# Main_PCB_v2.net
KiCad netlist of a schematic drawn in EAGLE
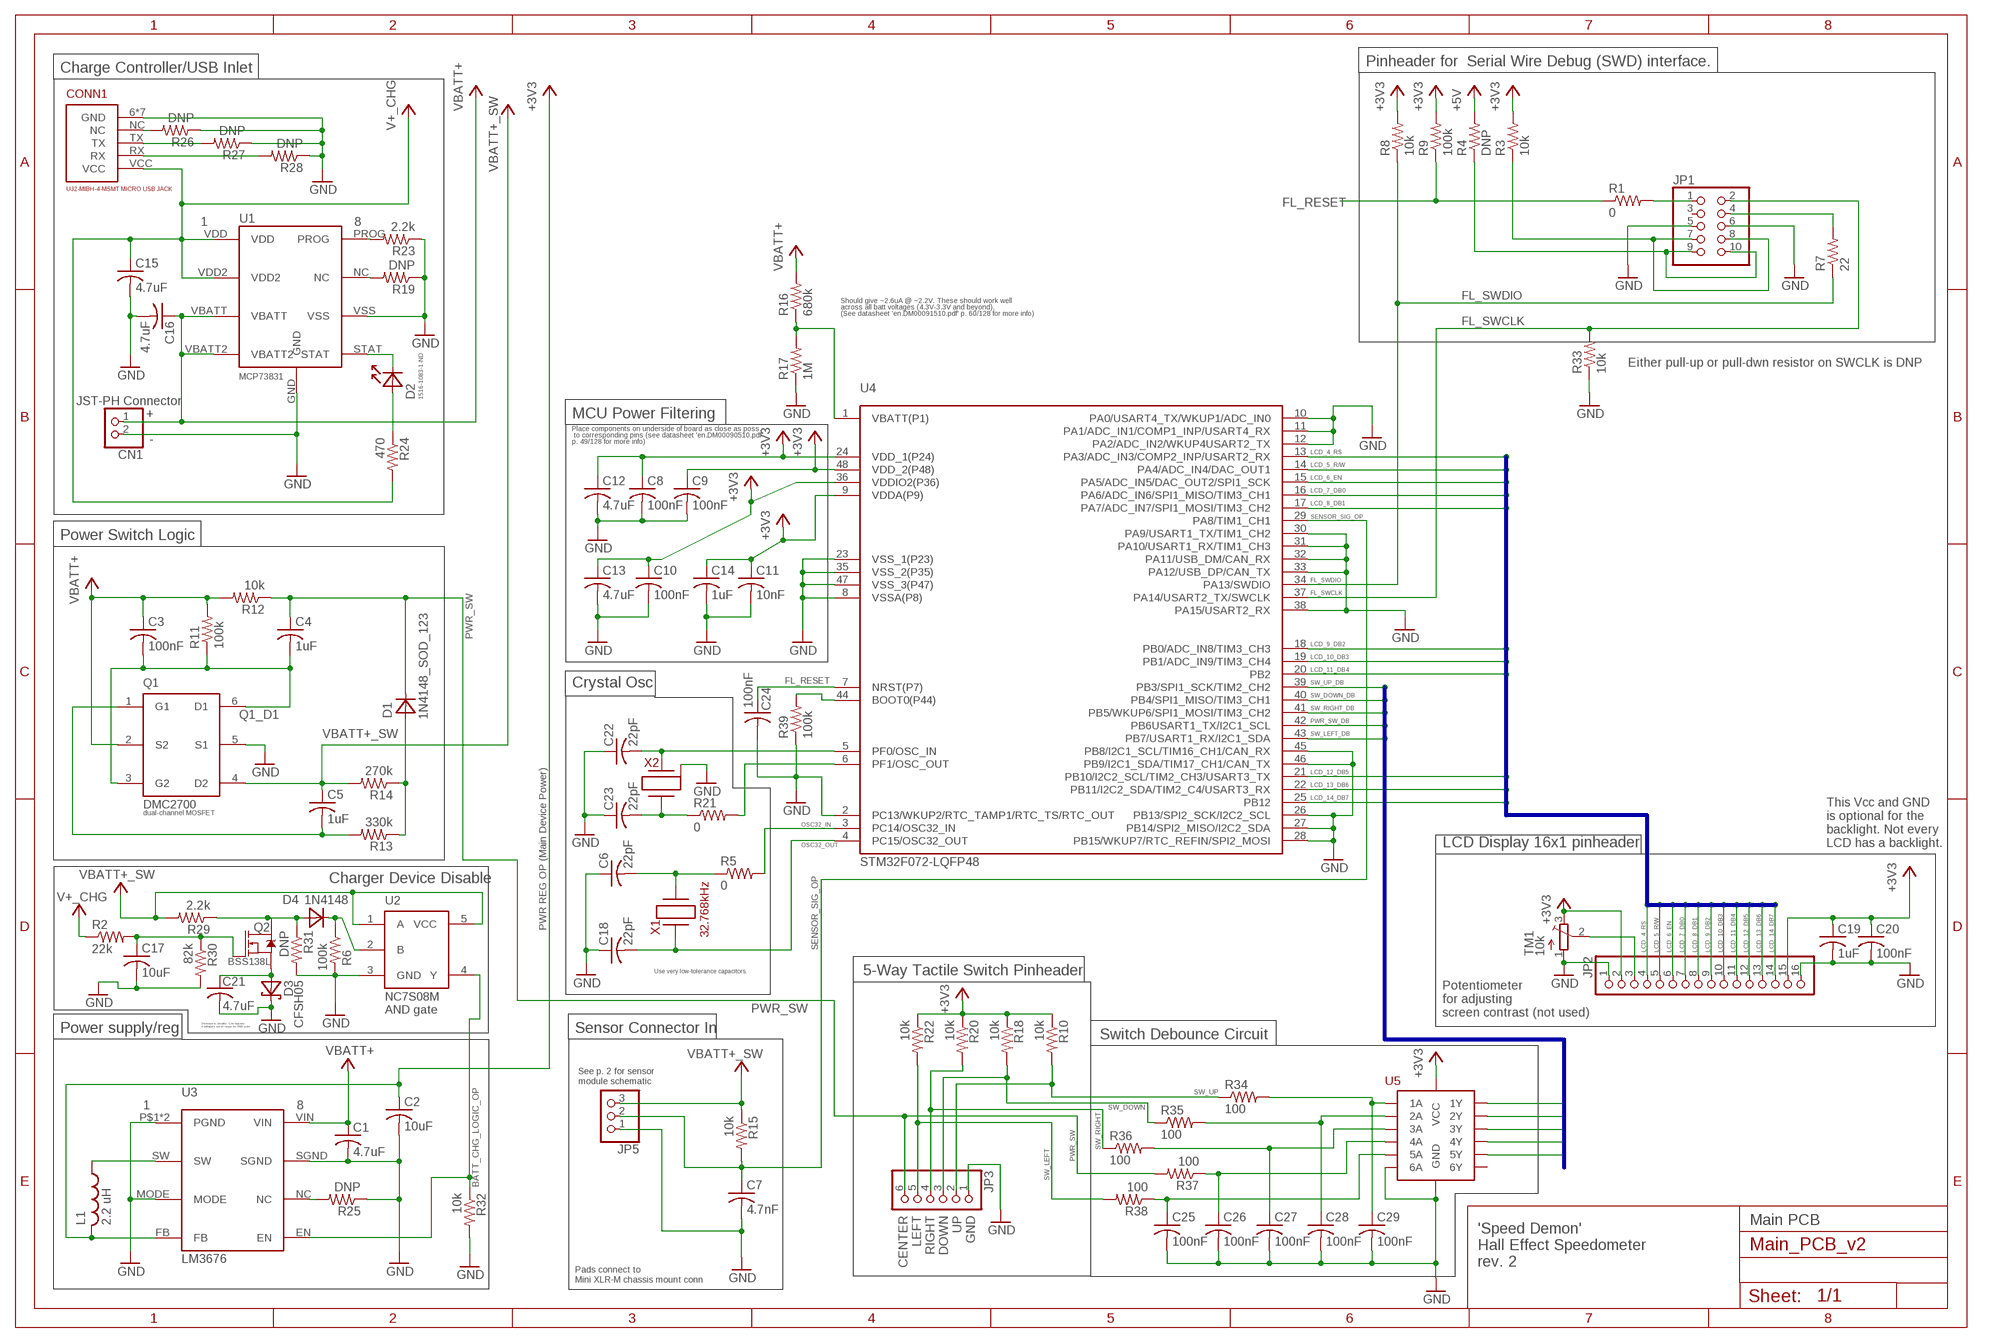
[diagram p0: schematic, sheet 1]

(export (version "E")
  (design (tool "Eeschema 10.0.6"))
  (components
    (comp (ref "C1")
      (value "4.7uF")
      (footprint "eagle-import:C_0805")
      (libsource (lib "eagle-import") (part "C_0805_NP"))
    )
    (comp (ref "C2")
      (value "10uF")
      (footprint "eagle-import:C_0805")
      (libsource (lib "eagle-import") (part "C_0805_NP"))
    )
    (comp (ref "C3")
      (value "100nF")
      (footprint "eagle-import:C_0805")
      (libsource (lib "eagle-import") (part "C_0805_NP"))
    )
    (comp (ref "C4")
      (value "1uF")
      (footprint "eagle-import:C_0805")
      (libsource (lib "eagle-import") (part "C_0805_NP"))
    )
    (comp (ref "C5")
      (value "1uF")
      (footprint "eagle-import:C_0805")
      (libsource (lib "eagle-import") (part "C_0805_NP"))
    )
    (comp (ref "C6")
      (value "22pF")
      (footprint "eagle-import:C_0805")
      (libsource (lib "eagle-import") (part "LCRD_SMD_generics_C_0805_NP"))
    )
    (comp (ref "C7")
      (value "4.7nF")
      (footprint "eagle-import:C_0805")
      (libsource (lib "eagle-import") (part "C_0805_NP"))
    )
    (comp (ref "C8")
      (value "100nF")
      (footprint "eagle-import:C_0805")
      (libsource (lib "eagle-import") (part "C_0805_NP"))
    )
    (comp (ref "C9")
      (value "100nF")
      (footprint "eagle-import:C_0805")
      (libsource (lib "eagle-import") (part "C_0805_NP"))
    )
    (comp (ref "C10")
      (value "100nF")
      (footprint "eagle-import:C_0805")
      (libsource (lib "eagle-import") (part "C_0805_NP"))
    )
    (comp (ref "C11")
      (value "10nF")
      (footprint "eagle-import:C_0805")
      (libsource (lib "eagle-import") (part "C_0805_NP"))
    )
    (comp (ref "C12")
      (value "4.7uF")
      (footprint "eagle-import:C_0805")
      (libsource (lib "eagle-import") (part "C_0805_NP"))
    )
    (comp (ref "C13")
      (value "4.7uF")
      (footprint "eagle-import:C_0805")
      (libsource (lib "eagle-import") (part "C_0805_NP"))
    )
    (comp (ref "C14")
      (value "1uF")
      (footprint "eagle-import:C_0805")
      (libsource (lib "eagle-import") (part "C_0805_NP"))
    )
    (comp (ref "C15")
      (value "4.7uF")
      (footprint "eagle-import:C_0805")
      (libsource (lib "eagle-import") (part "C_0805_NP"))
    )
    (comp (ref "C16")
      (value "4.7uF")
      (footprint "eagle-import:C_0805")
      (libsource (lib "eagle-import") (part "C_0805_NP"))
    )
    (comp (ref "C17")
      (value "10uF")
      (footprint "eagle-import:C_0805")
      (libsource (lib "eagle-import") (part "C_0805_NP"))
    )
    (comp (ref "C18")
      (value "22pF")
      (footprint "eagle-import:C_0805")
      (libsource (lib "eagle-import") (part "LCRD_SMD_generics_C_0805_NP"))
    )
    (comp (ref "C19")
      (value "1uF")
      (footprint "eagle-import:C_0805")
      (libsource (lib "eagle-import") (part "C_0805_NP"))
    )
    (comp (ref "C20")
      (value "100nF")
      (footprint "eagle-import:C_0805")
      (libsource (lib "eagle-import") (part "C_0805_NP"))
    )
    (comp (ref "C21")
      (value "4.7uF")
      (footprint "eagle-import:C_0805")
      (libsource (lib "eagle-import") (part "C_0805_NP"))
    )
    (comp (ref "C22")
      (value "22pF")
      (footprint "eagle-import:C_0805")
      (libsource (lib "eagle-import") (part "LCRD_SMD_generics_C_0805_NP"))
    )
    (comp (ref "C23")
      (value "22pF")
      (footprint "eagle-import:C_0805")
      (libsource (lib "eagle-import") (part "LCRD_SMD_generics_C_0805_NP"))
    )
    (comp (ref "C24")
      (value "100nF")
      (footprint "eagle-import:C_0805")
      (libsource (lib "eagle-import") (part "C_0805_NP"))
    )
    (comp (ref "C25")
      (value "100nF")
      (footprint "eagle-import:C_0805")
      (libsource (lib "eagle-import") (part "C_0805_NP"))
    )
    (comp (ref "C26")
      (value "100nF")
      (footprint "eagle-import:C_0805")
      (libsource (lib "eagle-import") (part "C_0805_NP"))
    )
    (comp (ref "C27")
      (value "100nF")
      (footprint "eagle-import:C_0805")
      (libsource (lib "eagle-import") (part "C_0805_NP"))
    )
    (comp (ref "C28")
      (value "100nF")
      (footprint "eagle-import:C_0805")
      (libsource (lib "eagle-import") (part "C_0805_NP"))
    )
    (comp (ref "C29")
      (value "100nF")
      (footprint "eagle-import:C_0805")
      (libsource (lib "eagle-import") (part "C_0805_NP"))
    )
    (comp (ref "CN1")
      (value "JST_2PIN-SMT-RA")
      (footprint "eagle-import:JST-PH-2-SMT-RA")
      (libsource (lib "eagle-import") (part "JST_2PIN-SMT-RA"))
    )
    (comp (ref "CONN1")
      (value "USB_JACK_102-4008-1-ND_USB-MICRO-B")
      (footprint "eagle-import:USB_JACK_102-4008-1-ND_UJ2-MIBH-4-MSMT-TR")
      (libsource (lib "eagle-import") (part "USB_JACK_102-4008-1-ND_USB-MICRO-B"))
    )
    (comp (ref "D1")
      (value "1N4148_SOD_123")
      (footprint "eagle-import:D_SOD_123")
      (libsource (lib "eagle-import") (part "1N4148_SOD_123"))
    )
    (comp (ref "D2")
      (value "LED_0805")
      (footprint "eagle-import:LED_0805")
      (libsource (lib "eagle-import") (part "LED_0805"))
    )
    (comp (ref "D3")
      (value "CFSH05")
      (footprint "eagle-import:SOD-882")
      (libsource (lib "eagle-import") (part "CFSH05_SCHOTTKY"))
    )
    (comp (ref "D4")
      (value "1N4148")
      (footprint "eagle-import:D_SOD_123")
      (libsource (lib "eagle-import") (part "1N4148_SOD_123"))
    )
    (comp (ref "JP1")
      (value "PINHD-2X5")
      (footprint "eagle-import:2X05")
      (libsource (lib "eagle-import") (part "PINHD-2X5"))
    )
    (comp (ref "JP2")
      (value "PINHD-1X16")
      (footprint "eagle-import:1X16")
      (libsource (lib "eagle-import") (part "PINHD-1X16"))
    )
    (comp (ref "JP3")
      (value "PINHD-1X6")
      (footprint "eagle-import:1X06")
      (libsource (lib "eagle-import") (part "PINHD-1X6"))
    )
    (comp (ref "JP5")
      (value "PINHD-1X3")
      (footprint "eagle-import:1X03")
      (libsource (lib "eagle-import") (part "PINHD-1X3"))
    )
    (comp (ref "L1")
      (value "2.2 uH")
      (footprint "eagle-import:NONSTANDARD_IND")
      (libsource (lib "eagle-import") (part "NRS4010T2R2MDGGV"))
    )
    (comp (ref "Q1")
      (value "DMC2700")
      (footprint "eagle-import:SOT-23-6")
      (libsource (lib "eagle-import") (part "DMC2700_SOT-23-6"))
    )
    (comp (ref "Q2")
      (value "BSS138L")
      (footprint "eagle-import:TO-236")
      (libsource (lib "eagle-import") (part "BSS138LT1_TO-236"))
    )
    (comp (ref "R1")
      (value "0")
      (footprint "eagle-import:R0805")
      (libsource (lib "eagle-import") (part "R-US_R0805"))
    )
    (comp (ref "R2")
      (value "22k")
      (footprint "eagle-import:R_0805")
      (libsource (lib "eagle-import") (part "R_0805"))
    )
    (comp (ref "R3")
      (value "10k")
      (footprint "eagle-import:R0805")
      (libsource (lib "eagle-import") (part "R-US_R0805"))
    )
    (comp (ref "R4")
      (value "DNP")
      (footprint "eagle-import:R0805")
      (libsource (lib "eagle-import") (part "R-US_R0805"))
    )
    (comp (ref "R5")
      (value "0")
      (footprint "eagle-import:R0805")
      (libsource (lib "eagle-import") (part "R-US_R0805"))
    )
    (comp (ref "R6")
      (value "100k")
      (footprint "eagle-import:R_0805")
      (libsource (lib "eagle-import") (part "R_0805"))
    )
    (comp (ref "R7")
      (value "22")
      (footprint "eagle-import:R0805")
      (libsource (lib "eagle-import") (part "R-US_R0805"))
    )
    (comp (ref "R8")
      (value "10k")
      (footprint "eagle-import:R0805")
      (libsource (lib "eagle-import") (part "R-US_R0805"))
    )
    (comp (ref "R9")
      (value "100k")
      (footprint "eagle-import:R0805")
      (libsource (lib "eagle-import") (part "R-US_R0805"))
    )
    (comp (ref "R10")
      (value "10k")
      (footprint "eagle-import:R_0805")
      (libsource (lib "eagle-import") (part "R_0805"))
    )
    (comp (ref "R11")
      (value "100k")
      (footprint "eagle-import:R_0805")
      (libsource (lib "eagle-import") (part "R_0805"))
    )
    (comp (ref "R12")
      (value "10k")
      (footprint "eagle-import:R_0805")
      (libsource (lib "eagle-import") (part "R_0805"))
    )
    (comp (ref "R13")
      (value "330k")
      (footprint "eagle-import:R_0805")
      (libsource (lib "eagle-import") (part "R_0805"))
    )
    (comp (ref "R14")
      (value "270k")
      (footprint "eagle-import:R_0805")
      (libsource (lib "eagle-import") (part "R_0805"))
    )
    (comp (ref "R15")
      (value "10k")
      (footprint "eagle-import:R_0805")
      (libsource (lib "eagle-import") (part "R_0805"))
    )
    (comp (ref "R16")
      (value "680k")
      (footprint "eagle-import:R_0805")
      (libsource (lib "eagle-import") (part "R_0805"))
    )
    (comp (ref "R17")
      (value "1M")
      (footprint "eagle-import:R_0805")
      (libsource (lib "eagle-import") (part "R_0805"))
    )
    (comp (ref "R18")
      (value "10k")
      (footprint "eagle-import:R_0805")
      (libsource (lib "eagle-import") (part "R_0805"))
    )
    (comp (ref "R19")
      (value "DNP")
      (footprint "eagle-import:R_0805")
      (libsource (lib "eagle-import") (part "R_0805"))
    )
    (comp (ref "R20")
      (value "10k")
      (footprint "eagle-import:R_0805")
      (libsource (lib "eagle-import") (part "R_0805"))
    )
    (comp (ref "R21")
      (value "0")
      (footprint "eagle-import:R_0805")
      (libsource (lib "eagle-import") (part "LCRD_SMD_generics_R_0805"))
    )
    (comp (ref "R22")
      (value "10k")
      (footprint "eagle-import:R_0805")
      (libsource (lib "eagle-import") (part "R_0805"))
    )
    (comp (ref "R23")
      (value "2.2k")
      (footprint "eagle-import:R_0805")
      (libsource (lib "eagle-import") (part "R_0805"))
    )
    (comp (ref "R24")
      (value "470")
      (footprint "eagle-import:R_0805")
      (libsource (lib "eagle-import") (part "R_0805"))
    )
    (comp (ref "R25")
      (value "DNP")
      (footprint "eagle-import:R_0805")
      (libsource (lib "eagle-import") (part "R_0805"))
    )
    (comp (ref "R26")
      (value "DNP")
      (footprint "eagle-import:R_0805")
      (libsource (lib "eagle-import") (part "R_0805"))
    )
    (comp (ref "R27")
      (value "DNP")
      (footprint "eagle-import:R_0805")
      (libsource (lib "eagle-import") (part "R_0805"))
    )
    (comp (ref "R28")
      (value "DNP")
      (footprint "eagle-import:R_0805")
      (libsource (lib "eagle-import") (part "R_0805"))
    )
    (comp (ref "R29")
      (value "2.2k")
      (footprint "eagle-import:R_0805")
      (libsource (lib "eagle-import") (part "R_0805"))
    )
    (comp (ref "R30")
      (value "82k")
      (footprint "eagle-import:R_0805")
      (libsource (lib "eagle-import") (part "R_0805"))
    )
    (comp (ref "R31")
      (value "DNP")
      (footprint "eagle-import:R_0805")
      (libsource (lib "eagle-import") (part "R_0805"))
    )
    (comp (ref "R32")
      (value "10k")
      (footprint "eagle-import:R_0805")
      (libsource (lib "eagle-import") (part "R_0805"))
    )
    (comp (ref "R33")
      (value "10k")
      (footprint "eagle-import:R0805")
      (libsource (lib "eagle-import") (part "R-US_R0805"))
    )
    (comp (ref "R34")
      (value "100")
      (footprint "eagle-import:R_0805")
      (libsource (lib "eagle-import") (part "R_0805"))
    )
    (comp (ref "R35")
      (value "100")
      (footprint "eagle-import:R_0805")
      (libsource (lib "eagle-import") (part "R_0805"))
    )
    (comp (ref "R36")
      (value "100")
      (footprint "eagle-import:R_0805")
      (libsource (lib "eagle-import") (part "R_0805"))
    )
    (comp (ref "R37")
      (value "100")
      (footprint "eagle-import:R_0805")
      (libsource (lib "eagle-import") (part "R_0805"))
    )
    (comp (ref "R38")
      (value "100")
      (footprint "eagle-import:R_0805")
      (libsource (lib "eagle-import") (part "R_0805"))
    )
    (comp (ref "R39")
      (value "100k")
      (footprint "eagle-import:R_0805")
      (libsource (lib "eagle-import") (part "LCRD_SMD_generics_R_0805"))
    )
    (comp (ref "TM1")
      (value "10k")
      (footprint "eagle-import:TRIM-3386")
      (libsource (lib "eagle-import") (part "TRIMPOT3386"))
    )
    (comp (ref "U1")
      (value "MCP73831_8-DFN")
      (footprint "eagle-import:8-DFN-(2X3)")
      (libsource (lib "eagle-import") (part "MCP73831_8-DFN"))
    )
    (comp (ref "U2")
      (value "NC7S08M")
      (footprint "eagle-import:SOT-23-5")
      (libsource (lib "eagle-import") (part "NC7S08_SOT_23_5"))
    )
    (comp (ref "U3")
      (value "LM3676")
      (footprint "eagle-import:WSON")
      (libsource (lib "eagle-import") (part "LM3676"))
    )
    (comp (ref "U4")
      (value "STM32F072-LQFP48")
      (footprint "eagle-import:LQFP48")
      (libsource (lib "eagle-import") (part "STM32F072-LQFP48"))
    )
    (comp (ref "U5")
      (value "SN74LV14A_HEX_SHMITT")
      (footprint "eagle-import:S-PVFQN-N14")
      (libsource (lib "eagle-import") (part "SN74LV14A_HEX_SHMITT"))
    )
    (comp (ref "X1")
      (value "32.768kHz")
      (footprint "eagle-import:CRYSTAL_OSC_3.2X1.5")
      (libsource (lib "eagle-import") (part "XC2292CT-ND"))
    )
    (comp (ref "X2")
      (value "ABM3B-8.000MHZ-10-D-1-G-T")
      (footprint "eagle-import:4-SMD")
      (libsource (lib "eagle-import") (part "ABM3B-8.000MHZ-10-D-1-G-T"))
    )
  )
  (nets
    (net (code "1") (name "+3V3") (class "Default")
      (node (ref "C10") (pin "1") (pinfunction "1_1") (pintype "passive"))
      (node (ref "C11") (pin "1") (pinfunction "1_1") (pintype "passive"))
      (node (ref "C12") (pin "1") (pinfunction "1_1") (pintype "passive"))
      (node (ref "C13") (pin "1") (pinfunction "1_1") (pintype "passive"))
      (node (ref "C14") (pin "1") (pinfunction "1_1") (pintype "passive"))
      (node (ref "C19") (pin "1") (pinfunction "1_1") (pintype "passive"))
      (node (ref "C2") (pin "1") (pinfunction "1_1") (pintype "passive"))
      (node (ref "C20") (pin "1") (pinfunction "1_1") (pintype "passive"))
      (node (ref "C8") (pin "1") (pinfunction "1_1") (pintype "passive"))
      (node (ref "C9") (pin "1") (pinfunction "1_1") (pintype "passive"))
      (node (ref "JP2") (pin "15") (pinfunction "15_15") (pintype "passive"))
      (node (ref "JP2") (pin "2") (pinfunction "2_2") (pintype "passive"))
      (node (ref "L1") (pin "P$2") (pinfunction "2_P$2") (pintype "passive"))
      (node (ref "R10") (pin "1") (pinfunction "1_1") (pintype "passive"))
      (node (ref "R18") (pin "1") (pinfunction "1_1") (pintype "passive"))
      (node (ref "R20") (pin "1") (pinfunction "1_1") (pintype "passive"))
      (node (ref "R22") (pin "1") (pinfunction "1_1") (pintype "passive"))
      (node (ref "R3") (pin "2") (pinfunction "2_2") (pintype "passive"))
      (node (ref "R8") (pin "2") (pinfunction "2_2") (pintype "passive"))
      (node (ref "R9") (pin "2") (pinfunction "2_2") (pintype "passive"))
      (node (ref "TM1") (pin "3") (pinfunction "E_3") (pintype "passive"))
      (node (ref "U3") (pin "FB") (pinfunction "FB_FB") (pintype "bidirectional"))
      (node (ref "U4") (pin "24") (pinfunction "VDD_1(P24)_24") (pintype "bidirectional"))
      (node (ref "U4") (pin "36") (pinfunction "VDDIO2(P36)_36") (pintype "bidirectional"))
      (node (ref "U4") (pin "48") (pinfunction "VDD_2(P48)_48") (pintype "bidirectional"))
      (node (ref "U4") (pin "9") (pinfunction "VDDA(P9)_9") (pintype "bidirectional"))
      (node (ref "U5") (pin "P$14") (pinfunction "VCC_P$14") (pintype "power_in"))
    )
    (net (code "2") (name "+5V") (class "Default")
      (node (ref "R4") (pin "2") (pinfunction "2_2") (pintype "passive"))
    )
    (net (code "3") (name "/BATT_CHG_LOGIC_OP") (class "Default")
      (node (ref "R32") (pin "1") (pinfunction "1_1") (pintype "passive"))
      (node (ref "U2") (pin "4") (pinfunction "Y_4") (pintype "bidirectional"))
      (node (ref "U3") (pin "EN") (pinfunction "EN_EN") (pintype "bidirectional"))
    )
    (net (code "4") (name "/FL_RESET") (class "Default")
      (node (ref "C24") (pin "1") (pinfunction "1_1") (pintype "passive"))
      (node (ref "R1") (pin "1") (pinfunction "1_1") (pintype "passive"))
      (node (ref "R9") (pin "1") (pinfunction "1_1") (pintype "passive"))
      (node (ref "U4") (pin "7") (pinfunction "NRST(P7)_7") (pintype "bidirectional"))
    )
    (net (code "5") (name "/FL_SWCLK") (class "Default")
      (node (ref "JP1") (pin "2") (pinfunction "2_2") (pintype "passive"))
      (node (ref "R33") (pin "2") (pinfunction "2_2") (pintype "passive"))
      (node (ref "U4") (pin "37") (pinfunction "PA14/USART2_TX/SWCLK_37") (pintype "bidirectional"))
    )
    (net (code "6") (name "/FL_SWDIO") (class "Default")
      (node (ref "R7") (pin "1") (pinfunction "1_1") (pintype "passive"))
      (node (ref "R8") (pin "1") (pinfunction "1_1") (pintype "passive"))
      (node (ref "U4") (pin "34") (pinfunction "PA13/SWDIO_34") (pintype "bidirectional"))
    )
    (net (code "7") (name "/LCD_4_RS") (class "Default")
      (node (ref "JP2") (pin "4") (pinfunction "4_4") (pintype "passive"))
      (node (ref "U4") (pin "13") (pinfunction "PA3/ADC_IN3/COMP2_INP/USART2_RX_13") (pintype "bidirectional"))
    )
    (net (code "8") (name "/LCD_5_R{slash}W") (class "Default")
      (node (ref "JP2") (pin "5") (pinfunction "5_5") (pintype "passive"))
      (node (ref "U4") (pin "14") (pinfunction "PA4/ADC_IN4/DAC_OUT1_14") (pintype "bidirectional"))
    )
    (net (code "9") (name "/LCD_6_EN") (class "Default")
      (node (ref "JP2") (pin "6") (pinfunction "6_6") (pintype "passive"))
      (node (ref "U4") (pin "15") (pinfunction "PA5/ADC_IN5/DAC_OUT2/SPI1_SCK_15") (pintype "bidirectional"))
    )
    (net (code "10") (name "/LCD_7_DB0") (class "Default")
      (node (ref "JP2") (pin "7") (pinfunction "7_7") (pintype "passive"))
      (node (ref "U4") (pin "16") (pinfunction "PA6/ADC_IN6/SPI1_MISO/TIM3_CH1_16") (pintype "bidirectional"))
    )
    (net (code "11") (name "/LCD_8_DB1") (class "Default")
      (node (ref "JP2") (pin "8") (pinfunction "8_8") (pintype "passive"))
      (node (ref "U4") (pin "17") (pinfunction "PA7/ADC_IN7/SPI1_MOSI/TIM3_CH2_17") (pintype "bidirectional"))
    )
    (net (code "12") (name "/LCD_9_DB2") (class "Default")
      (node (ref "JP2") (pin "9") (pinfunction "9_9") (pintype "passive"))
      (node (ref "U4") (pin "18") (pinfunction "PB0/ADC_IN8/TIM3_CH3_18") (pintype "bidirectional"))
    )
    (net (code "13") (name "/LCD_10_DB3") (class "Default")
      (node (ref "JP2") (pin "10") (pinfunction "10_10") (pintype "passive"))
      (node (ref "U4") (pin "19") (pinfunction "PB1/ADC_IN9/TIM3_CH4_19") (pintype "bidirectional"))
    )
    (net (code "14") (name "/LCD_11_DB4") (class "Default")
      (node (ref "JP2") (pin "11") (pinfunction "11_11") (pintype "passive"))
      (node (ref "U4") (pin "20") (pinfunction "PB2_20") (pintype "bidirectional"))
    )
    (net (code "15") (name "/LCD_12_DB5") (class "Default")
      (node (ref "JP2") (pin "12") (pinfunction "12_12") (pintype "passive"))
      (node (ref "U4") (pin "21") (pinfunction "PB10/I2C2_SCL/TIM2_CH3/USART3_TX_21") (pintype "bidirectional"))
    )
    (net (code "16") (name "/LCD_13_DB6") (class "Default")
      (node (ref "JP2") (pin "13") (pinfunction "13_13") (pintype "passive"))
      (node (ref "U4") (pin "22") (pinfunction "PB11/I2C2_SDA/TIM2_C4/USART3_RX_22") (pintype "bidirectional"))
    )
    (net (code "17") (name "/LCD_14_DB7") (class "Default")
      (node (ref "JP2") (pin "14") (pinfunction "14_14") (pintype "passive"))
      (node (ref "U4") (pin "25") (pinfunction "PB12_25") (pintype "bidirectional"))
    )
    (net (code "18") (name "/OSC32_IN") (class "Default")
      (node (ref "C6") (pin "2") (pinfunction "2_2") (pintype "passive"))
      (node (ref "R5") (pin "1") (pinfunction "1_1") (pintype "passive"))
      (node (ref "X1") (pin "P$1") (pinfunction "1_P$1") (pintype "bidirectional"))
    )
    (net (code "19") (name "/OSC32_OUT") (class "Default")
      (node (ref "C18") (pin "2") (pinfunction "2_2") (pintype "passive"))
      (node (ref "U4") (pin "4") (pinfunction "PC15/OSC32_OUT_4") (pintype "bidirectional"))
      (node (ref "X1") (pin "P$2") (pinfunction "2_P$2") (pintype "bidirectional"))
    )
    (net (code "20") (name "/PWR_SW") (class "Default")
      (node (ref "C4") (pin "1") (pinfunction "1_1") (pintype "passive"))
      (node (ref "D1") (pin "2") (pinfunction "C_2") (pintype "passive"))
      (node (ref "JP3") (pin "6") (pinfunction "6_6") (pintype "passive"))
      (node (ref "R12") (pin "1") (pinfunction "1_1") (pintype "passive"))
      (node (ref "R37") (pin "2") (pinfunction "2_2") (pintype "passive"))
    )
    (net (code "21") (name "/PWR_SW_DB") (class "Default")
      (node (ref "U4") (pin "42") (pinfunction "PB6USART1_TX/I2C1_SCL_42") (pintype "bidirectional"))
      (node (ref "U5") (pin "P$8") (pinfunction "4Y_P$8") (pintype "bidirectional"))
    )
    (net (code "22") (name "/Q1_D1") (class "Default")
      (node (ref "C3") (pin "2") (pinfunction "2_2") (pintype "passive"))
      (node (ref "C4") (pin "2") (pinfunction "2_2") (pintype "passive"))
      (node (ref "Q1") (pin "3") (pinfunction "G2_3") (pintype "bidirectional"))
      (node (ref "Q1") (pin "6") (pinfunction "D1_6") (pintype "bidirectional"))
      (node (ref "R11") (pin "1") (pinfunction "1_1") (pintype "passive"))
    )
    (net (code "23") (name "/SENSOR_SIG_OP") (class "Default")
      (node (ref "C7") (pin "1") (pinfunction "1_1") (pintype "passive"))
      (node (ref "JP5") (pin "2") (pinfunction "2_2") (pintype "passive"))
      (node (ref "R15") (pin "2") (pinfunction "2_2") (pintype "passive"))
      (node (ref "U4") (pin "29") (pinfunction "PA8/TIM1_CH1_29") (pintype "bidirectional"))
    )
    (net (code "24") (name "/SW_DOWN") (class "Default")
      (node (ref "JP3") (pin "3") (pinfunction "3_3") (pintype "passive"))
      (node (ref "R18") (pin "2") (pinfunction "2_2") (pintype "passive"))
      (node (ref "R35") (pin "1") (pinfunction "1_1") (pintype "passive"))
    )
    (net (code "25") (name "/SW_DOWN_DB") (class "Default")
      (node (ref "U4") (pin "40") (pinfunction "PB4/SPI1_MISO/TIM3_CH1_40") (pintype "bidirectional"))
      (node (ref "U5") (pin "P$4") (pinfunction "2Y_P$4") (pintype "bidirectional"))
    )
    (net (code "26") (name "/SW_LEFT") (class "Default")
      (node (ref "JP3") (pin "5") (pinfunction "5_5") (pintype "passive"))
      (node (ref "R22") (pin "2") (pinfunction "2_2") (pintype "passive"))
      (node (ref "R38") (pin "2") (pinfunction "2_2") (pintype "passive"))
    )
    (net (code "27") (name "/SW_LEFT_DB") (class "Default")
      (node (ref "U4") (pin "43") (pinfunction "PB7/USART1_RX/I2C1_SDA_43") (pintype "bidirectional"))
      (node (ref "U5") (pin "P$10") (pinfunction "5Y_P$10") (pintype "bidirectional"))
    )
    (net (code "28") (name "/SW_RIGHT") (class "Default")
      (node (ref "JP3") (pin "4") (pinfunction "4_4") (pintype "passive"))
      (node (ref "R20") (pin "2") (pinfunction "2_2") (pintype "passive"))
      (node (ref "R36") (pin "1") (pinfunction "1_1") (pintype "passive"))
    )
    (net (code "29") (name "/SW_RIGHT_DB") (class "Default")
      (node (ref "U4") (pin "41") (pinfunction "PB5/WKUP6/SPI1_MOSI/TIM3_CH2_41") (pintype "bidirectional"))
      (node (ref "U5") (pin "P$6") (pinfunction "3Y_P$6") (pintype "bidirectional"))
    )
    (net (code "30") (name "/SW_UP") (class "Default")
      (node (ref "JP3") (pin "2") (pinfunction "2_2") (pintype "passive"))
      (node (ref "R10") (pin "2") (pinfunction "2_2") (pintype "passive"))
      (node (ref "R34") (pin "1") (pinfunction "1_1") (pintype "passive"))
    )
    (net (code "31") (name "/SW_UP_DB") (class "Default")
      (node (ref "U4") (pin "39") (pinfunction "PB3/SPI1_SCK/TIM2_CH2_39") (pintype "bidirectional"))
      (node (ref "U5") (pin "P$2") (pinfunction "1Y_P$2") (pintype "bidirectional"))
    )
    (net (code "32") (name "GND") (class "Default")
      (node (ref "C1") (pin "2") (pinfunction "2_2") (pintype "passive"))
      (node (ref "C10") (pin "2") (pinfunction "2_2") (pintype "passive"))
      (node (ref "C11") (pin "2") (pinfunction "2_2") (pintype "passive"))
      (node (ref "C12") (pin "2") (pinfunction "2_2") (pintype "passive"))
      (node (ref "C13") (pin "2") (pinfunction "2_2") (pintype "passive"))
      (node (ref "C14") (pin "2") (pinfunction "2_2") (pintype "passive"))
      (node (ref "C15") (pin "2") (pinfunction "2_2") (pintype "passive"))
      (node (ref "C16") (pin "2") (pinfunction "2_2") (pintype "passive"))
      (node (ref "C17") (pin "2") (pinfunction "2_2") (pintype "passive"))
      (node (ref "C18") (pin "1") (pinfunction "1_1") (pintype "passive"))
      (node (ref "C19") (pin "2") (pinfunction "2_2") (pintype "passive"))
      (node (ref "C2") (pin "2") (pinfunction "2_2") (pintype "passive"))
      (node (ref "C20") (pin "2") (pinfunction "2_2") (pintype "passive"))
      (node (ref "C21") (pin "2") (pinfunction "2_2") (pintype "passive"))
      (node (ref "C22") (pin "1") (pinfunction "1_1") (pintype "passive"))
      (node (ref "C23") (pin "1") (pinfunction "1_1") (pintype "passive"))
      (node (ref "C24") (pin "2") (pinfunction "2_2") (pintype "passive"))
      (node (ref "C25") (pin "2") (pinfunction "2_2") (pintype "passive"))
      (node (ref "C26") (pin "2") (pinfunction "2_2") (pintype "passive"))
      (node (ref "C27") (pin "2") (pinfunction "2_2") (pintype "passive"))
      (node (ref "C28") (pin "2") (pinfunction "2_2") (pintype "passive"))
      (node (ref "C29") (pin "2") (pinfunction "2_2") (pintype "passive"))
      (node (ref "C6") (pin "1") (pinfunction "1_1") (pintype "passive"))
      (node (ref "C7") (pin "2") (pinfunction "2_2") (pintype "passive"))
      (node (ref "C8") (pin "2") (pinfunction "2_2") (pintype "passive"))
      (node (ref "C9") (pin "2") (pinfunction "2_2") (pintype "passive"))
      (node (ref "CN1") (pin "2") (pinfunction "1_2") (pintype "passive"))
      (node (ref "CONN1") (pin "10") (pinfunction "GND_10") (pintype "bidirectional"))
      (node (ref "CONN1") (pin "11") (pinfunction "GND_11") (pintype "bidirectional"))
      (node (ref "CONN1") (pin "6") (pinfunction "GND_6") (pintype "bidirectional"))
      (node (ref "CONN1") (pin "7") (pinfunction "GND_7") (pintype "bidirectional"))
      (node (ref "CONN1") (pin "8") (pinfunction "GND_8") (pintype "bidirectional"))
      (node (ref "CONN1") (pin "9") (pinfunction "GND_9") (pintype "bidirectional"))
      (node (ref "CONN1") (pin "GND") (pinfunction "GND_GND") (pintype "bidirectional"))
      (node (ref "D3") (pin "P$2") (pinfunction "C_P$2") (pintype "passive"))
      (node (ref "JP1") (pin "5") (pinfunction "5_5") (pintype "passive"))
      (node (ref "JP1") (pin "6") (pinfunction "6_6") (pintype "passive"))
      (node (ref "JP2") (pin "1") (pinfunction "1_1") (pintype "passive"))
      (node (ref "JP2") (pin "16") (pinfunction "16_16") (pintype "passive"))
      (node (ref "JP3") (pin "1") (pinfunction "1_1") (pintype "passive"))
      (node (ref "JP5") (pin "1") (pinfunction "1_1") (pintype "passive"))
      (node (ref "Q1") (pin "5") (pinfunction "S1_5") (pintype "bidirectional"))
      (node (ref "R17") (pin "1") (pinfunction "1_1") (pintype "passive"))
      (node (ref "R19") (pin "1") (pinfunction "1_1") (pintype "passive"))
      (node (ref "R23") (pin "1") (pinfunction "1_1") (pintype "passive"))
      (node (ref "R25") (pin "1") (pinfunction "1_1") (pintype "passive"))
      (node (ref "R26") (pin "1") (pinfunction "1_1") (pintype "passive"))
      (node (ref "R27") (pin "1") (pinfunction "1_1") (pintype "passive"))
      (node (ref "R28") (pin "1") (pinfunction "1_1") (pintype "passive"))
      (node (ref "R30") (pin "2") (pinfunction "2_2") (pintype "passive"))
      (node (ref "R31") (pin "2") (pinfunction "2_2") (pintype "passive"))
      (node (ref "R32") (pin "2") (pinfunction "2_2") (pintype "passive"))
      (node (ref "R33") (pin "1") (pinfunction "1_1") (pintype "passive"))
      (node (ref "R39") (pin "1") (pinfunction "1_1") (pintype "passive"))
      (node (ref "R6") (pin "2") (pinfunction "2_2") (pintype "passive"))
      (node (ref "TM1") (pin "1") (pinfunction "A_1") (pintype "passive"))
      (node (ref "U1") (pin "GND") (pinfunction "GND_GND") (pintype "bidirectional"))
      (node (ref "U1") (pin "VSS") (pinfunction "VSS_VSS") (pintype "bidirectional"))
      (node (ref "U2") (pin "3") (pinfunction "GND_3") (pintype "bidirectional"))
      (node (ref "U3") (pin "MODE") (pinfunction "MODE_MODE") (pintype "bidirectional"))
      (node (ref "U3") (pin "P$1") (pinfunction "PGND_P$1") (pintype "power_in"))
      (node (ref "U3") (pin "PGND") (pinfunction "PGND_PGND") (pintype "power_in"))
      (node (ref "U3") (pin "SGND") (pinfunction "SGND_SGND") (pintype "power_in"))
      (node (ref "U4") (pin "10") (pinfunction "PA0/USART4_TX/WKUP1/ADC_IN0_10") (pintype "bidirectional"))
      (node (ref "U4") (pin "11") (pinfunction "PA1/ADC_IN1/COMP1_INP/USART4_RX_11") (pintype "bidirectional"))
      (node (ref "U4") (pin "12") (pinfunction "PA2/ADC_IN2/WKUP4USART2_TX_12") (pintype "bidirectional"))
      (node (ref "U4") (pin "2") (pinfunction "PC13/WKUP2/RTC_TAMP1/RTC_TS/RTC_OUT_2") (pintype "bidirectional"))
      (node (ref "U4") (pin "23") (pinfunction "VSS_1(P23)_23") (pintype "bidirectional"))
      (node (ref "U4") (pin "26") (pinfunction "PB13/SPI2_SCK/I2C2_SCL_26") (pintype "bidirectional"))
      (node (ref "U4") (pin "27") (pinfunction "PB14/SPI2_MISO/I2C2_SDA_27") (pintype "bidirectional"))
      (node (ref "U4") (pin "28") (pinfunction "PB15/WKUP7/RTC_REFIN/SPI2_MOSI_28") (pintype "bidirectional"))
      (node (ref "U4") (pin "30") (pinfunction "PA9/USART1_TX/TIM1_CH2_30") (pintype "bidirectional"))
      (node (ref "U4") (pin "31") (pinfunction "PA10/USART1_RX/TIM1_CH3_31") (pintype "bidirectional"))
      (node (ref "U4") (pin "32") (pinfunction "PA11/USB_DM/CAN_RX_32") (pintype "bidirectional"))
      (node (ref "U4") (pin "33") (pinfunction "PA12/USB_DP/CAN_TX_33") (pintype "bidirectional"))
      (node (ref "U4") (pin "35") (pinfunction "VSS_2(P35)_35") (pintype "bidirectional"))
      (node (ref "U4") (pin "38") (pinfunction "PA15/USART2_RX_38") (pintype "bidirectional"))
      (node (ref "U4") (pin "45") (pinfunction "PB8/I2C1_SCL/TIM16_CH1/CAN_RX_45") (pintype "bidirectional"))
      (node (ref "U4") (pin "46") (pinfunction "PB9/I2C1_SDA/TIM17_CH1/CAN_TX_46") (pintype "bidirectional"))
      (node (ref "U4") (pin "47") (pinfunction "VSS_3(P47)_47") (pintype "bidirectional"))
      (node (ref "U4") (pin "8") (pinfunction "VSSA(P8)_8") (pintype "bidirectional"))
      (node (ref "U5") (pin "GND") (pinfunction "GND_GND") (pintype "power_in"))
      (node (ref "U5") (pin "P$13") (pinfunction "6A_P$13") (pintype "bidirectional"))
      (node (ref "U5") (pin "P$7") (pinfunction "GND_P$7") (pintype "power_in"))
      (node (ref "X2") (pin "P$02") (pinfunction "P$1_P$02") (pintype "bidirectional"))
      (node (ref "X2") (pin "P$04") (pinfunction "P$1_P$04") (pintype "bidirectional"))
    )
    (net (code "33") (name "Net-(CONN1-PadNC)") (class "Default")
      (node (ref "CONN1") (pin "NC") (pinfunction "NC_NC") (pintype "bidirectional"))
      (node (ref "R26") (pin "2") (pinfunction "2_2") (pintype "passive"))
    )
    (net (code "34") (name "Net-(CONN1-PadRX)") (class "Default")
      (node (ref "CONN1") (pin "RX") (pinfunction "RX_RX") (pintype "bidirectional"))
      (node (ref "R28") (pin "2") (pinfunction "2_2") (pintype "passive"))
    )
    (net (code "35") (name "Net-(CONN1-PadTX)") (class "Default")
      (node (ref "CONN1") (pin "TX") (pinfunction "TX_TX") (pintype "bidirectional"))
      (node (ref "R27") (pin "2") (pinfunction "2_2") (pintype "passive"))
    )
    (net (code "36") (name "Net-(D1-A)") (class "Default")
      (node (ref "D1") (pin "1") (pinfunction "A_1") (pintype "passive"))
      (node (ref "R13") (pin "1") (pinfunction "1_1") (pintype "passive"))
      (node (ref "R14") (pin "1") (pinfunction "1_1") (pintype "passive"))
    )
    (net (code "37") (name "Net-(D2-A)") (class "Default")
      (node (ref "D2") (pin "1") (pinfunction "A_1") (pintype "passive"))
      (node (ref "R24") (pin "1") (pinfunction "1_1") (pintype "passive"))
    )
    (net (code "38") (name "Net-(D2-C)") (class "Default")
      (node (ref "D2") (pin "2") (pinfunction "C_2") (pintype "passive"))
      (node (ref "U1") (pin "STAT") (pinfunction "STAT_STAT") (pintype "bidirectional"))
    )
    (net (code "39") (name "Net-(D3-A)") (class "Default")
      (node (ref "C21") (pin "1") (pinfunction "1_1") (pintype "passive"))
      (node (ref "D3") (pin "P$1") (pinfunction "A_P$1") (pintype "passive"))
      (node (ref "Q2") (pin "2") (pinfunction "S_2") (pintype "bidirectional"))
    )
    (net (code "40") (name "Net-(D4-A)") (class "Default")
      (node (ref "D4") (pin "1") (pinfunction "A_1") (pintype "passive"))
      (node (ref "Q2") (pin "3") (pinfunction "D_3") (pintype "bidirectional"))
      (node (ref "R29") (pin "1") (pinfunction "1_1") (pintype "passive"))
      (node (ref "R31") (pin "1") (pinfunction "1_1") (pintype "passive"))
    )
    (net (code "41") (name "Net-(D4-C)") (class "Default")
      (node (ref "D4") (pin "2") (pinfunction "C_2") (pintype "passive"))
      (node (ref "R6") (pin "1") (pinfunction "1_1") (pintype "passive"))
      (node (ref "U2") (pin "2") (pinfunction "B_2") (pintype "bidirectional"))
    )
    (net (code "42") (name "Net-(JP1-Pad1)") (class "Default")
      (node (ref "JP1") (pin "1") (pinfunction "1_1") (pintype "passive"))
      (node (ref "R1") (pin "2") (pinfunction "2_2") (pintype "passive"))
    )
    (net (code "43") (name "Net-(JP1-Pad4)") (class "Default")
      (node (ref "JP1") (pin "4") (pinfunction "4_4") (pintype "passive"))
      (node (ref "R7") (pin "2") (pinfunction "2_2") (pintype "passive"))
    )
    (net (code "44") (name "Net-(JP1-Pad7)") (class "Default")
      (node (ref "JP1") (pin "7") (pinfunction "7_7") (pintype "passive"))
      (node (ref "JP1") (pin "8") (pinfunction "8_8") (pintype "passive"))
      (node (ref "R3") (pin "1") (pinfunction "1_1") (pintype "passive"))
    )
    (net (code "45") (name "Net-(JP1-Pad10)") (class "Default")
      (node (ref "JP1") (pin "10") (pinfunction "10_10") (pintype "passive"))
      (node (ref "JP1") (pin "9") (pinfunction "9_9") (pintype "passive"))
      (node (ref "R4") (pin "1") (pinfunction "1_1") (pintype "passive"))
    )
    (net (code "46") (name "Net-(L1-1)") (class "Default")
      (node (ref "L1") (pin "P$1") (pinfunction "1_P$1") (pintype "passive"))
      (node (ref "U3") (pin "SW") (pinfunction "SW_SW") (pintype "bidirectional"))
    )
    (net (code "47") (name "Net-(Q1-G1)") (class "Default")
      (node (ref "C5") (pin "2") (pinfunction "2_2") (pintype "passive"))
      (node (ref "Q1") (pin "1") (pinfunction "G1_1") (pintype "bidirectional"))
      (node (ref "R13") (pin "2") (pinfunction "2_2") (pintype "passive"))
    )
    (net (code "48") (name "Net-(Q2-G)") (class "Default")
      (node (ref "C17") (pin "1") (pinfunction "1_1") (pintype "passive"))
      (node (ref "Q2") (pin "1") (pinfunction "G_1") (pintype "bidirectional"))
      (node (ref "R2") (pin "2") (pinfunction "2_2") (pintype "passive"))
      (node (ref "R30") (pin "1") (pinfunction "1_1") (pintype "passive"))
    )
    (net (code "49") (name "Net-(R19-Pad2)") (class "Default")
      (node (ref "R19") (pin "2") (pinfunction "2_2") (pintype "passive"))
      (node (ref "U1") (pin "NC") (pinfunction "NC_NC") (pintype "power_in"))
    )
    (net (code "50") (name "Net-(R23-Pad2)") (class "Default")
      (node (ref "R23") (pin "2") (pinfunction "2_2") (pintype "passive"))
      (node (ref "U1") (pin "PROG") (pinfunction "PROG_PROG") (pintype "bidirectional"))
    )
    (net (code "51") (name "Net-(R25-Pad2)") (class "Default")
      (node (ref "R25") (pin "2") (pinfunction "2_2") (pintype "passive"))
      (node (ref "U3") (pin "NC") (pinfunction "NC_NC") (pintype "bidirectional"))
    )
    (net (code "52") (name "Net-(TM1-S)") (class "Default")
      (node (ref "JP2") (pin "3") (pinfunction "3_3") (pintype "passive"))
      (node (ref "TM1") (pin "2") (pinfunction "S_2") (pintype "passive"))
    )
    (net (code "53") (name "Net-(U4-BOOT0(P44))") (class "Default")
      (node (ref "R39") (pin "2") (pinfunction "2_2") (pintype "passive"))
      (node (ref "U4") (pin "44") (pinfunction "BOOT0(P44)_44") (pintype "bidirectional"))
    )
    (net (code "54") (name "Net-(U4-PC14{slash}OSC32_IN)") (class "Default")
      (node (ref "R5") (pin "2") (pinfunction "2_2") (pintype "passive"))
      (node (ref "U4") (pin "3") (pinfunction "PC14/OSC32_IN_3") (pintype "bidirectional"))
    )
    (net (code "55") (name "Net-(U4-PF0{slash}OSC_IN)") (class "Default")
      (node (ref "C22") (pin "2") (pinfunction "2_2") (pintype "passive"))
      (node (ref "U4") (pin "5") (pinfunction "PF0/OSC_IN_5") (pintype "bidirectional"))
      (node (ref "X2") (pin "P$01") (pinfunction "1_P$01") (pintype "bidirectional"))
    )
    (net (code "56") (name "Net-(U4-PF1{slash}OSC_OUT)") (class "Default")
      (node (ref "R21") (pin "2") (pinfunction "2_2") (pintype "passive"))
      (node (ref "U4") (pin "6") (pinfunction "PF1/OSC_OUT_6") (pintype "bidirectional"))
    )
    (net (code "57") (name "Net-(U4-VBATT(P1))") (class "Default")
      (node (ref "R16") (pin "1") (pinfunction "1_1") (pintype "passive"))
      (node (ref "R17") (pin "2") (pinfunction "2_2") (pintype "passive"))
      (node (ref "U4") (pin "1") (pinfunction "VBATT(P1)_1") (pintype "bidirectional"))
    )
    (net (code "58") (name "Net-(U5-1A)") (class "Default")
      (node (ref "C29") (pin "1") (pinfunction "1_1") (pintype "passive"))
      (node (ref "R34") (pin "2") (pinfunction "2_2") (pintype "passive"))
      (node (ref "U5") (pin "P$1") (pinfunction "1A_P$1") (pintype "bidirectional"))
    )
    (net (code "59") (name "Net-(U5-2A)") (class "Default")
      (node (ref "C28") (pin "1") (pinfunction "1_1") (pintype "passive"))
      (node (ref "R35") (pin "2") (pinfunction "2_2") (pintype "passive"))
      (node (ref "U5") (pin "P$3") (pinfunction "2A_P$3") (pintype "bidirectional"))
    )
    (net (code "60") (name "Net-(U5-3A)") (class "Default")
      (node (ref "C27") (pin "1") (pinfunction "1_1") (pintype "passive"))
      (node (ref "R36") (pin "2") (pinfunction "2_2") (pintype "passive"))
      (node (ref "U5") (pin "P$5") (pinfunction "3A_P$5") (pintype "bidirectional"))
    )
    (net (code "61") (name "Net-(U5-4A)") (class "Default")
      (node (ref "C26") (pin "1") (pinfunction "1_1") (pintype "passive"))
      (node (ref "R37") (pin "1") (pinfunction "1_1") (pintype "passive"))
      (node (ref "U5") (pin "P$9") (pinfunction "4A_P$9") (pintype "bidirectional"))
    )
    (net (code "62") (name "Net-(U5-5A)") (class "Default")
      (node (ref "C25") (pin "1") (pinfunction "1_1") (pintype "passive"))
      (node (ref "R38") (pin "1") (pinfunction "1_1") (pintype "passive"))
      (node (ref "U5") (pin "P$11") (pinfunction "5A_P$11") (pintype "bidirectional"))
    )
    (net (code "63") (name "Net-(X2-2)") (class "Default")
      (node (ref "C23") (pin "2") (pinfunction "2_2") (pintype "passive"))
      (node (ref "R21") (pin "1") (pinfunction "1_1") (pintype "passive"))
      (node (ref "X2") (pin "P$03") (pinfunction "2_P$03") (pintype "bidirectional"))
    )
    (net (code "64") (name "V+_CHG") (class "Default")
      (node (ref "C15") (pin "1") (pinfunction "1_1") (pintype "passive"))
      (node (ref "CONN1") (pin "VCC") (pinfunction "VCC_VCC") (pintype "bidirectional"))
      (node (ref "R2") (pin "1") (pinfunction "1_1") (pintype "passive"))
      (node (ref "R24") (pin "2") (pinfunction "2_2") (pintype "passive"))
      (node (ref "U1") (pin "VDD") (pinfunction "VDD_VDD") (pintype "power_in"))
      (node (ref "U1") (pin "VDD2") (pinfunction "VDD2_VDD2") (pintype "bidirectional"))
    )
    (net (code "65") (name "VBATT+") (class "Default")
      (node (ref "C1") (pin "1") (pinfunction "1_1") (pintype "passive"))
      (node (ref "C16") (pin "1") (pinfunction "1_1") (pintype "passive"))
      (node (ref "C3") (pin "1") (pinfunction "1_1") (pintype "passive"))
      (node (ref "CN1") (pin "1") (pinfunction "2_1") (pintype "passive"))
      (node (ref "Q1") (pin "2") (pinfunction "S2_2") (pintype "bidirectional"))
      (node (ref "R11") (pin "2") (pinfunction "2_2") (pintype "passive"))
      (node (ref "R12") (pin "2") (pinfunction "2_2") (pintype "passive"))
      (node (ref "R16") (pin "2") (pinfunction "2_2") (pintype "passive"))
      (node (ref "U1") (pin "VBATT") (pinfunction "VBATT_VBATT") (pintype "bidirectional"))
      (node (ref "U1") (pin "VBATT2") (pinfunction "VBATT2_VBATT2") (pintype "bidirectional"))
      (node (ref "U3") (pin "VIN") (pinfunction "VIN_VIN") (pintype "bidirectional"))
    )
    (net (code "66") (name "VBATT+_SW") (class "Default")
      (node (ref "C5") (pin "1") (pinfunction "1_1") (pintype "passive"))
      (node (ref "JP5") (pin "3") (pinfunction "3_3") (pintype "passive"))
      (node (ref "Q1") (pin "4") (pinfunction "D2_4") (pintype "bidirectional"))
      (node (ref "R14") (pin "2") (pinfunction "2_2") (pintype "passive"))
      (node (ref "R15") (pin "1") (pinfunction "1_1") (pintype "passive"))
      (node (ref "R29") (pin "2") (pinfunction "2_2") (pintype "passive"))
      (node (ref "U2") (pin "1") (pinfunction "A_1") (pintype "bidirectional"))
      (node (ref "U2") (pin "5") (pinfunction "VCC_5") (pintype "bidirectional"))
    )
    (net (code "67") (name "unconnected-(JP1-Pad3)") (class "Default")
      (node (ref "JP1") (pin "3") (pinfunction "3_3") (pintype "passive"))
    )
    (net (code "68") (name "unconnected-(U5-6Y-PadP$12)") (class "Default")
      (node (ref "U5") (pin "P$12") (pinfunction "6Y_P$12") (pintype "bidirectional"))
    )
  )
)
